# SpecialMechanism.net
KiCad netlist of a schematic drawn in EAGLE
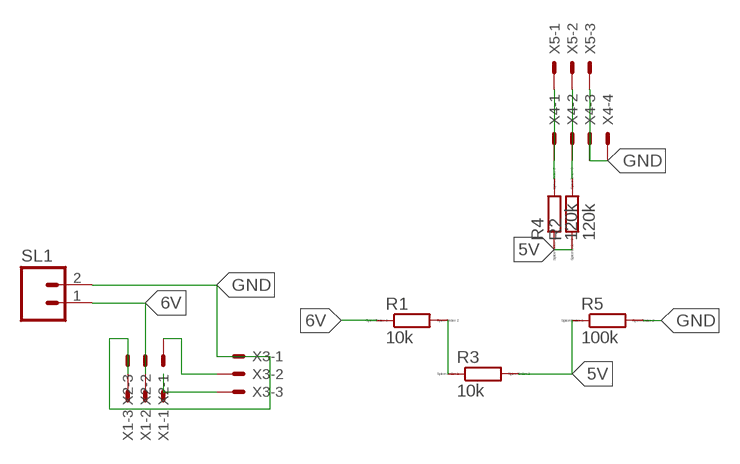
[diagram p0: schematic, sheet 1]

(export (version "E")
  (design (tool "Eeschema 10.0.6"))
  (components
    (comp (ref "R1")
      (value "10k")
      (footprint "eagle-import:0207_10")
      (libsource (lib "eagle-import") (part "R0207/10"))
    )
    (comp (ref "R2")
      (value "120k")
      (footprint "eagle-import:0207_10")
      (libsource (lib "eagle-import") (part "R0207/10"))
    )
    (comp (ref "R3")
      (value "10k")
      (footprint "eagle-import:0207_10")
      (libsource (lib "eagle-import") (part "R0207/10"))
    )
    (comp (ref "R4")
      (value "120k")
      (footprint "eagle-import:0207_10")
      (libsource (lib "eagle-import") (part "R0207/10"))
    )
    (comp (ref "R5")
      (value "100k")
      (footprint "eagle-import:0207_10")
      (libsource (lib "eagle-import") (part "R0207/10"))
    )
    (comp (ref "SL1")
      (value "M02")
      (footprint "eagle-import:02P")
      (libsource (lib "eagle-import") (part "M02"))
    )
    (comp (ref "X1")
      (value "KK-156-3")
      (footprint "eagle-import:KK-156-3")
      (fields (field (name "MF") "MOLEX"))
      (libsource (lib "eagle-import") (part "KK-156-3"))
    )
    (comp (ref "X2")
      (value "KK-156-3")
      (footprint "eagle-import:KK-156-3")
      (fields (field (name "MF") "MOLEX"))
      (libsource (lib "eagle-import") (part "KK-156-3"))
    )
    (comp (ref "X3")
      (value "KK-156-3")
      (footprint "eagle-import:KK-156-3")
      (fields (field (name "MF") "MOLEX"))
      (libsource (lib "eagle-import") (part "KK-156-3"))
    )
    (comp (ref "X4")
      (value "KK-156-4")
      (footprint "eagle-import:KK-156-4")
      (fields (field (name "MF") "MOLEX"))
      (libsource (lib "eagle-import") (part "KK-156-4"))
    )
    (comp (ref "X5")
      (value "KK-156-3")
      (footprint "eagle-import:KK-156-3")
      (fields (field (name "MF") "MOLEX"))
      (libsource (lib "eagle-import") (part "KK-156-3"))
    )
  )
  (nets
    (net (code "1") (name "5V") (class "Default")
      (node (ref "R2") (pin "1") (pinfunction "1_1") (pintype "passive"))
      (node (ref "R3") (pin "2") (pinfunction "2_2") (pintype "passive"))
      (node (ref "R4") (pin "1") (pinfunction "1_1") (pintype "passive"))
      (node (ref "R5") (pin "1") (pinfunction "1_1") (pintype "passive"))
    )
    (net (code "2") (name "6V") (class "Default")
      (node (ref "R1") (pin "1") (pinfunction "1_1") (pintype "passive"))
      (node (ref "SL1") (pin "1") (pinfunction "1_1") (pintype "passive"))
      (node (ref "X1") (pin "2") (pinfunction "S_2") (pintype "passive"))
      (node (ref "X2") (pin "2") (pinfunction "S_2") (pintype "passive"))
    )
    (net (code "3") (name "GND") (class "Default")
      (node (ref "R5") (pin "2") (pinfunction "2_2") (pintype "passive"))
      (node (ref "SL1") (pin "2") (pinfunction "2_2") (pintype "passive"))
      (node (ref "X1") (pin "3") (pinfunction "S_3") (pintype "passive"))
      (node (ref "X2") (pin "3") (pinfunction "S_3") (pintype "passive"))
      (node (ref "X3") (pin "1") (pinfunction "S_1") (pintype "passive"))
      (node (ref "X4") (pin "3") (pinfunction "S_3") (pintype "passive"))
      (node (ref "X4") (pin "4") (pinfunction "S_4") (pintype "passive"))
      (node (ref "X5") (pin "3") (pinfunction "S_3") (pintype "passive"))
    )
    (net (code "4") (name "Net-(R1-Pad2)") (class "Default")
      (node (ref "R1") (pin "2") (pinfunction "2_2") (pintype "passive"))
      (node (ref "R3") (pin "1") (pinfunction "1_1") (pintype "passive"))
    )
    (net (code "5") (name "Net-(X1A-S)") (class "Default")
      (node (ref "X1") (pin "1") (pinfunction "S_1") (pintype "passive"))
      (node (ref "X3") (pin "3") (pinfunction "S_3") (pintype "passive"))
    )
    (net (code "6") (name "Net-(X2A-S)") (class "Default")
      (node (ref "X2") (pin "1") (pinfunction "S_1") (pintype "passive"))
      (node (ref "X3") (pin "2") (pinfunction "S_2") (pintype "passive"))
    )
    (net (code "7") (name "Net-(X4A-S)") (class "Default")
      (node (ref "R4") (pin "2") (pinfunction "2_2") (pintype "passive"))
      (node (ref "X4") (pin "1") (pinfunction "S_1") (pintype "passive"))
      (node (ref "X5") (pin "1") (pinfunction "S_1") (pintype "passive"))
    )
    (net (code "8") (name "Net-(X4B-S)") (class "Default")
      (node (ref "R2") (pin "2") (pinfunction "2_2") (pintype "passive"))
      (node (ref "X4") (pin "2") (pinfunction "S_2") (pintype "passive"))
      (node (ref "X5") (pin "2") (pinfunction "S_2") (pintype "passive"))
    )
  )
)
